# plc_esp32_programmer.net
KiCad netlist of a schematic drawn in EAGLE
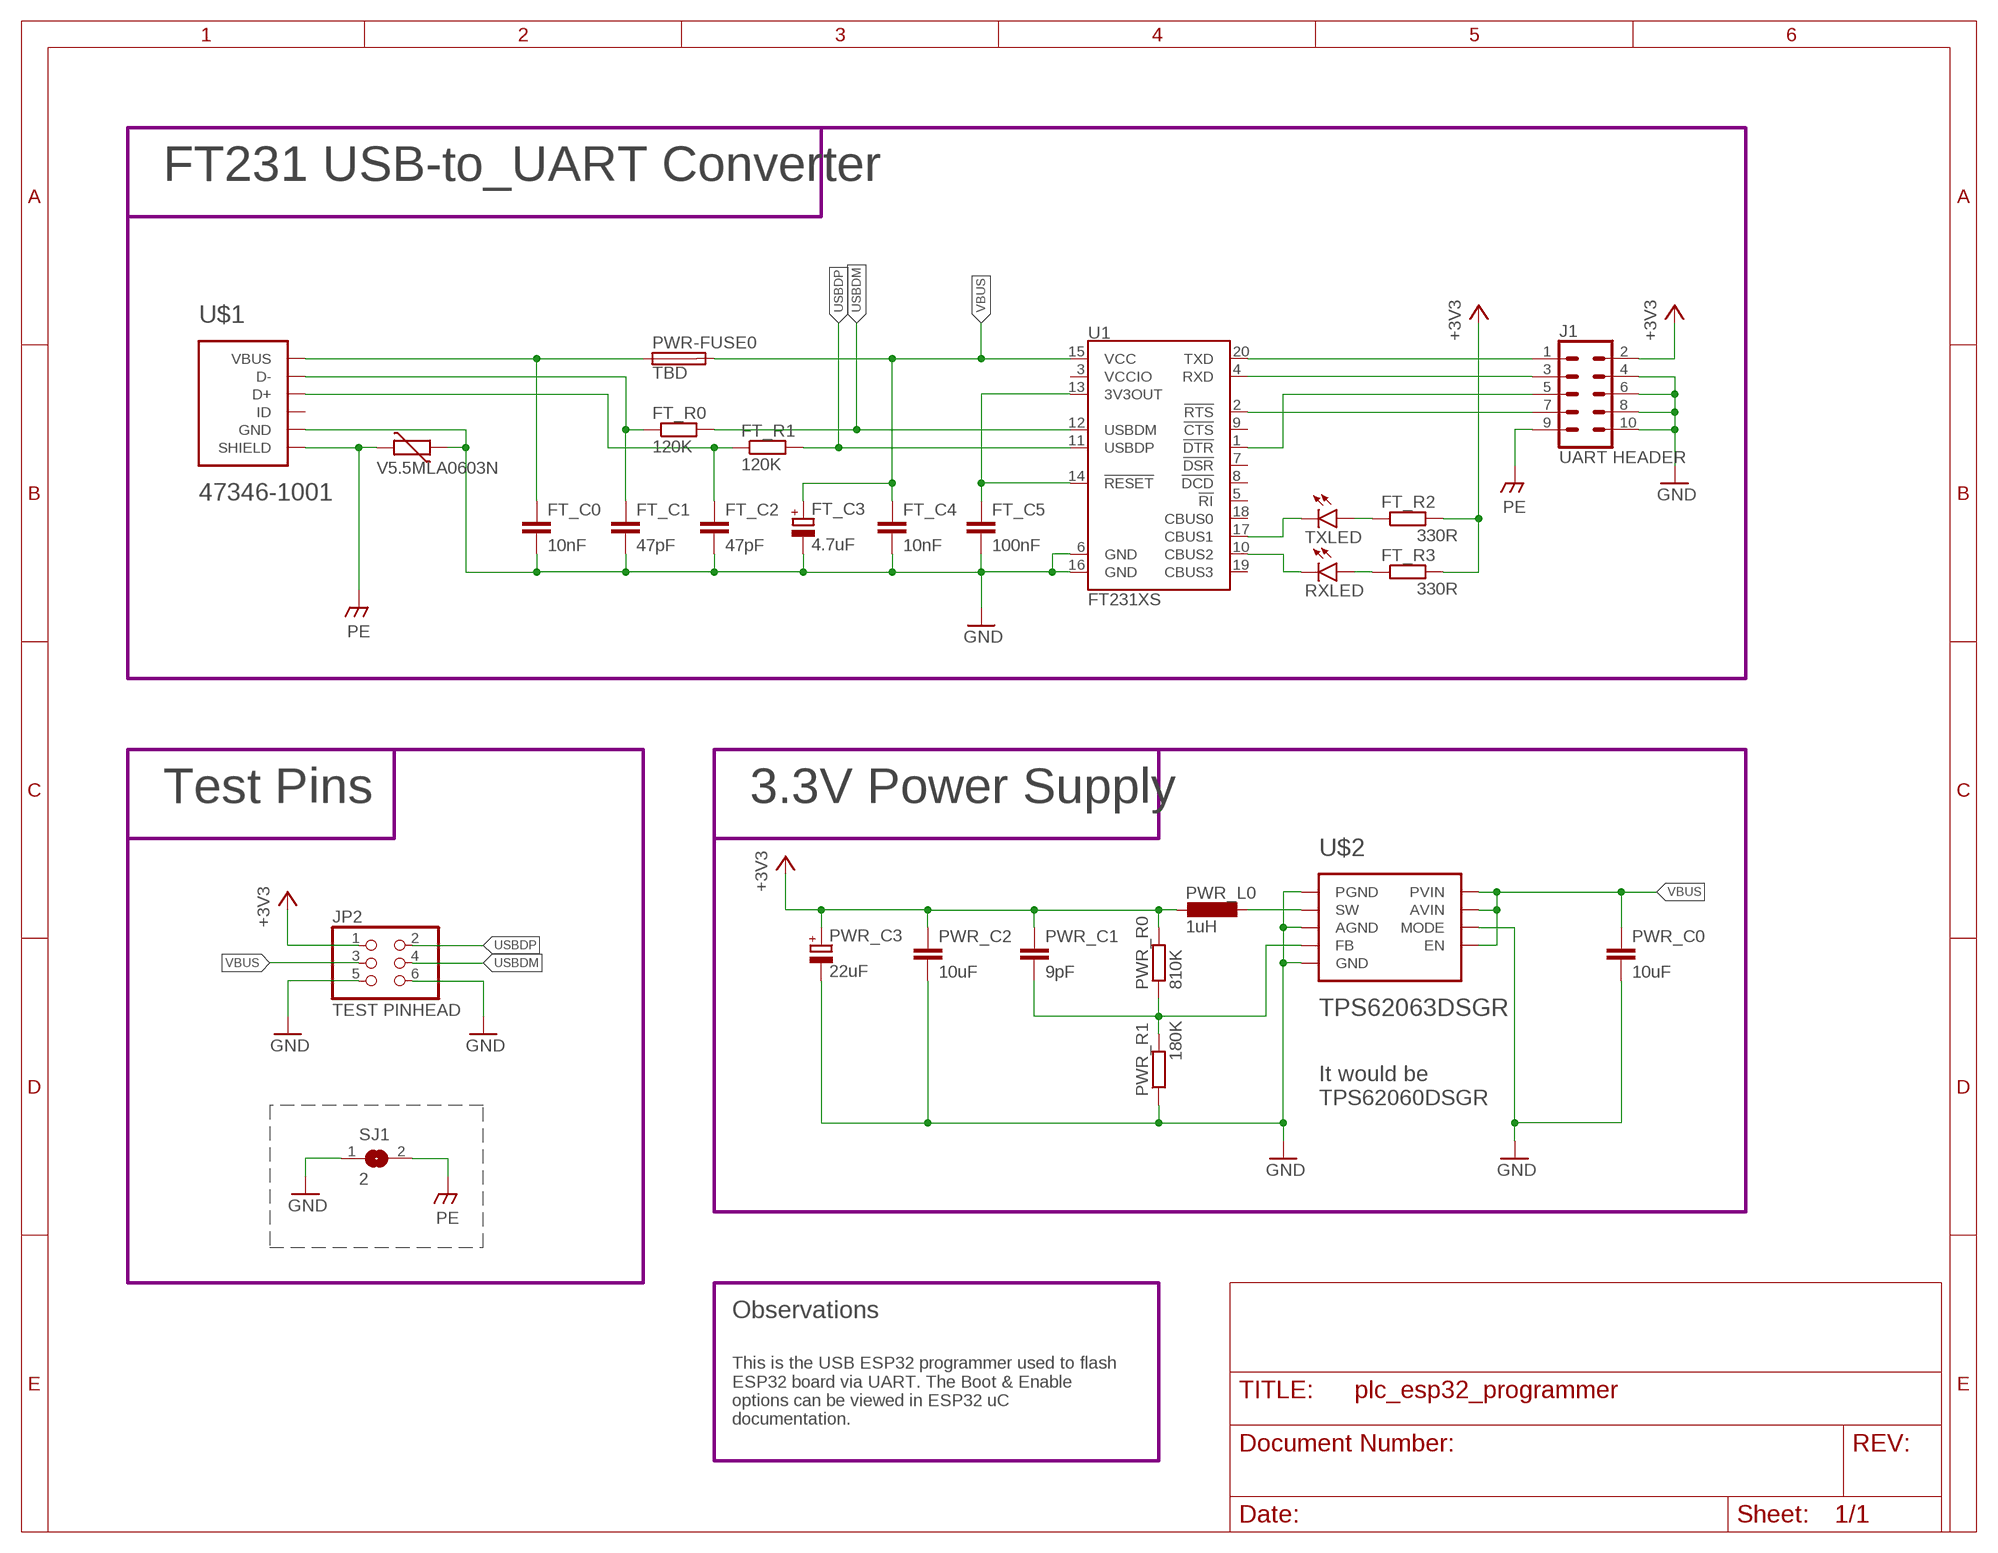
[diagram p0: schematic, sheet 1]

(export (version "E")
  (design (tool "Eeschema 10.0.6"))
  (components
    (comp (ref "FT_C0")
      (value "10nF")
      (footprint "eagle-import:C0402")
      (libsource (lib "eagle-import") (part "C-EUC0402"))
    )
    (comp (ref "FT_C1")
      (value "47pF")
      (footprint "eagle-import:C0402")
      (libsource (lib "eagle-import") (part "C-EUC0402"))
    )
    (comp (ref "FT_C2")
      (value "47pF")
      (footprint "eagle-import:C0402")
      (libsource (lib "eagle-import") (part "C-EUC0402"))
    )
    (comp (ref "FT_C3")
      (value "4.7uF")
      (footprint "eagle-import:SMC_B")
      (libsource (lib "eagle-import") (part "CPOL-EUSMCB"))
    )
    (comp (ref "FT_C4")
      (value "10nF")
      (footprint "eagle-import:C0402")
      (libsource (lib "eagle-import") (part "C-EUC0402"))
    )
    (comp (ref "FT_C5")
      (value "100nF")
      (footprint "eagle-import:C0402")
      (libsource (lib "eagle-import") (part "C-EUC0402"))
    )
    (comp (ref "FT_R0")
      (value "120K")
      (footprint "eagle-import:R0402")
      (libsource (lib "eagle-import") (part "R-EU_R0402"))
    )
    (comp (ref "FT_R1")
      (value "120K")
      (footprint "eagle-import:R0402")
      (libsource (lib "eagle-import") (part "R-EU_R0402"))
    )
    (comp (ref "FT_R2")
      (value "330R")
      (footprint "eagle-import:R0402")
      (libsource (lib "eagle-import") (part "R-EU_R0402"))
    )
    (comp (ref "FT_R3")
      (value "330R")
      (footprint "eagle-import:R0402")
      (libsource (lib "eagle-import") (part "R-EU_R0402"))
    )
    (comp (ref "J1")
      (value "UART HEADER")
      (footprint "eagle-import:2X5-SHROUDED_SMD")
      (libsource (lib "eagle-import") (part "CONN_05X2SHD_SMD"))
    )
    (comp (ref "JP2")
      (value "TEST PINHEAD")
      (footprint "eagle-import:2X03")
      (libsource (lib "eagle-import") (part "PINHD-2X3"))
    )
    (comp (ref "MCU_VAR1")
      (value "V5.5MLA0603N")
      (footprint "eagle-import:CT_CN0603")
      (libsource (lib "eagle-import") (part "VARISTORCN0603"))
    )
    (comp (ref "PWR-FUSE0")
      (value "TBD")
      (footprint "eagle-import:MF-SMDF050")
      (libsource (lib "eagle-import") (part "MF-SMDF050"))
    )
    (comp (ref "PWR_C0")
      (value "10uF")
      (footprint "eagle-import:C0603")
      (libsource (lib "eagle-import") (part "C-EUC0603"))
    )
    (comp (ref "PWR_C1")
      (value "9pF")
      (footprint "eagle-import:C0402")
      (libsource (lib "eagle-import") (part "C-EUC0402"))
    )
    (comp (ref "PWR_C2")
      (value "10uF")
      (footprint "eagle-import:C0603")
      (libsource (lib "eagle-import") (part "C-EUC0603"))
    )
    (comp (ref "PWR_C3")
      (value "22uF")
      (footprint "eagle-import:SMC_B")
      (libsource (lib "eagle-import") (part "CPOL-EUSMCB"))
    )
    (comp (ref "PWR_L0")
      (value "1uH")
      (footprint "eagle-import:L1210")
      (libsource (lib "eagle-import") (part "L-EUL1210"))
    )
    (comp (ref "PWR_R0")
      (value "810K")
      (footprint "eagle-import:R0402")
      (libsource (lib "eagle-import") (part "R-EU_R0402"))
    )
    (comp (ref "PWR_R1")
      (value "180K")
      (footprint "eagle-import:R0402")
      (libsource (lib "eagle-import") (part "R-EU_R0402"))
    )
    (comp (ref "RXLED")
      (value "LG_T679-E1F1-1")
      (footprint "eagle-import:PLCC2")
      (libsource (lib "eagle-import") (part "_T679-?-1E1F1LG"))
    )
    (comp (ref "SJ1") (value "2") (footprint "eagle-import:SJ") (libsource (lib "eagle-import") (part "SJ")))
    (comp (ref "TXLED")
      (value "LG_T679-E1F1-1")
      (footprint "eagle-import:PLCC2")
      (libsource (lib "eagle-import") (part "_T679-?-1E1F1LG"))
    )
    (comp (ref "U$1")
      (value "47346-1001")
      (footprint "eagle-import:47346-1001")
      (libsource (lib "eagle-import") (part "47346-1001"))
    )
    (comp (ref "U$2")
      (value "TPS62063DSGR")
      (footprint "eagle-import:WSON-8")
      (libsource (lib "eagle-import") (part "TPS62063DSGR"))
    )
    (comp (ref "U1")
      (value "FT231XS")
      (footprint "eagle-import:SSOP20_L")
      (libsource (lib "eagle-import") (part "FT231XS"))
    )
  )
  (nets
    (net (code "1") (name "+3V3") (class "Default")
      (node (ref "FT_R2") (pin "2") (pinfunction "2_2") (pintype "passive"))
      (node (ref "FT_R3") (pin "2") (pinfunction "2_2") (pintype "passive"))
      (node (ref "J1") (pin "2") (pinfunction "2_2") (pintype "passive"))
      (node (ref "JP2") (pin "1") (pinfunction "1_1") (pintype "passive"))
      (node (ref "PWR_C1") (pin "1") (pinfunction "1_1") (pintype "passive"))
      (node (ref "PWR_C2") (pin "1") (pinfunction "1_1") (pintype "passive"))
      (node (ref "PWR_C3") (pin "+") (pinfunction "+_+") (pintype "passive"))
      (node (ref "PWR_L0") (pin "2") (pinfunction "2_2") (pintype "passive"))
      (node (ref "PWR_R0") (pin "2") (pinfunction "2_2") (pintype "passive"))
    )
    (net (code "2") (name "GND") (class "Default")
      (node (ref "FT_C0") (pin "2") (pinfunction "2_2") (pintype "passive"))
      (node (ref "FT_C1") (pin "2") (pinfunction "2_2") (pintype "passive"))
      (node (ref "FT_C2") (pin "2") (pinfunction "2_2") (pintype "passive"))
      (node (ref "FT_C3") (pin "-") (pinfunction "-_-") (pintype "passive"))
      (node (ref "FT_C4") (pin "2") (pinfunction "2_2") (pintype "passive"))
      (node (ref "FT_C5") (pin "2") (pinfunction "2_2") (pintype "passive"))
      (node (ref "J1") (pin "10") (pinfunction "10_10") (pintype "passive"))
      (node (ref "J1") (pin "4") (pinfunction "4_4") (pintype "passive"))
      (node (ref "J1") (pin "6") (pinfunction "6_6") (pintype "passive"))
      (node (ref "J1") (pin "8") (pinfunction "8_8") (pintype "passive"))
      (node (ref "JP2") (pin "5") (pinfunction "5_5") (pintype "passive"))
      (node (ref "JP2") (pin "6") (pinfunction "6_6") (pintype "passive"))
      (node (ref "MCU_VAR1") (pin "1") (pinfunction "1_1") (pintype "passive"))
      (node (ref "PWR_C0") (pin "2") (pinfunction "2_2") (pintype "passive"))
      (node (ref "PWR_C2") (pin "2") (pinfunction "2_2") (pintype "passive"))
      (node (ref "PWR_C3") (pin "-") (pinfunction "-_-") (pintype "passive"))
      (node (ref "PWR_R1") (pin "1") (pinfunction "1_1") (pintype "passive"))
      (node (ref "SJ1") (pin "1") (pinfunction "1_1") (pintype "passive"))
      (node (ref "U$1") (pin "5") (pinfunction "GND_5") (pintype "bidirectional"))
      (node (ref "U$2") (pin "1") (pinfunction "PGND_1") (pintype "bidirectional"))
      (node (ref "U$2") (pin "10") (pinfunction "GND_10") (pintype "bidirectional"))
      (node (ref "U$2") (pin "11") (pinfunction "GND_11") (pintype "bidirectional"))
      (node (ref "U$2") (pin "3") (pinfunction "AGND_3") (pintype "bidirectional"))
      (node (ref "U$2") (pin "6") (pinfunction "MODE_6") (pintype "bidirectional"))
      (node (ref "U$2") (pin "9") (pinfunction "GND_9") (pintype "bidirectional"))
      (node (ref "U1") (pin "16") (pinfunction "GND_16") (pintype "bidirectional"))
      (node (ref "U1") (pin "6") (pinfunction "GND_6") (pintype "bidirectional"))
    )
    (net (code "3") (name "Net-(FT_R2-Pad1)") (class "Default")
      (node (ref "FT_R2") (pin "1") (pinfunction "1_1") (pintype "passive"))
      (node (ref "TXLED") (pin "A") (pinfunction "A_A") (pintype "passive"))
    )
    (net (code "4") (name "Net-(FT_R3-Pad1)") (class "Default")
      (node (ref "FT_R3") (pin "1") (pinfunction "1_1") (pintype "passive"))
      (node (ref "RXLED") (pin "A") (pinfunction "A_A") (pintype "passive"))
    )
    (net (code "5") (name "Net-(U$1-D+)") (class "Default")
      (node (ref "FT_C2") (pin "1") (pinfunction "1_1") (pintype "passive"))
      (node (ref "FT_R1") (pin "1") (pinfunction "1_1") (pintype "passive"))
      (node (ref "U$1") (pin "3") (pinfunction "D+_3") (pintype "bidirectional"))
    )
    (net (code "6") (name "Net-(U$1-D-)") (class "Default")
      (node (ref "FT_C1") (pin "1") (pinfunction "1_1") (pintype "passive"))
      (node (ref "FT_R0") (pin "1") (pinfunction "1_1") (pintype "passive"))
      (node (ref "U$1") (pin "2") (pinfunction "D-_2") (pintype "bidirectional"))
    )
    (net (code "7") (name "Net-(U$1-VBUS)") (class "Default")
      (node (ref "FT_C0") (pin "1") (pinfunction "1_1") (pintype "passive"))
      (node (ref "PWR-FUSE0") (pin "1") (pinfunction "1_1") (pintype "passive"))
      (node (ref "U$1") (pin "1") (pinfunction "VBUS_1") (pintype "bidirectional"))
    )
    (net (code "8") (name "Net-(U$2-FB)") (class "Default")
      (node (ref "PWR_C1") (pin "2") (pinfunction "2_2") (pintype "passive"))
      (node (ref "PWR_R0") (pin "1") (pinfunction "1_1") (pintype "passive"))
      (node (ref "PWR_R1") (pin "2") (pinfunction "2_2") (pintype "passive"))
      (node (ref "U$2") (pin "4") (pinfunction "FB_4") (pintype "bidirectional"))
    )
    (net (code "9") (name "Net-(U$2-SW)") (class "Default")
      (node (ref "PWR_L0") (pin "1") (pinfunction "1_1") (pintype "passive"))
      (node (ref "U$2") (pin "2") (pinfunction "SW_2") (pintype "bidirectional"))
    )
    (net (code "10") (name "Net-(U1-3V3OUT)") (class "Default")
      (node (ref "FT_C5") (pin "1") (pinfunction "1_1") (pintype "passive"))
      (node (ref "U1") (pin "13") (pinfunction "3V3OUT_13") (pintype "bidirectional"))
      (node (ref "U1") (pin "14") (pinfunction "~{RESET}_14") (pintype "bidirectional"))
    )
    (net (code "11") (name "Net-(U1-CBUS1)") (class "Default")
      (node (ref "TXLED") (pin "C") (pinfunction "C_C") (pintype "passive"))
      (node (ref "U1") (pin "17") (pinfunction "CBUS1_17") (pintype "bidirectional"))
    )
    (net (code "12") (name "Net-(U1-CBUS2)") (class "Default")
      (node (ref "RXLED") (pin "C") (pinfunction "C_C") (pintype "passive"))
      (node (ref "U1") (pin "10") (pinfunction "CBUS2_10") (pintype "bidirectional"))
    )
    (net (code "13") (name "Net-(U1-RXD)") (class "Default")
      (node (ref "J1") (pin "3") (pinfunction "3_3") (pintype "passive"))
      (node (ref "U1") (pin "4") (pinfunction "RXD_4") (pintype "bidirectional"))
    )
    (net (code "14") (name "Net-(U1-TXD)") (class "Default")
      (node (ref "J1") (pin "1") (pinfunction "1_1") (pintype "passive"))
      (node (ref "U1") (pin "20") (pinfunction "TXD_20") (pintype "bidirectional"))
    )
    (net (code "15") (name "Net-(U1-~{DTR})") (class "Default")
      (node (ref "J1") (pin "5") (pinfunction "5_5") (pintype "passive"))
      (node (ref "U1") (pin "1") (pinfunction "~{DTR}_1") (pintype "bidirectional"))
    )
    (net (code "16") (name "Net-(U1-~{RTS})") (class "Default")
      (node (ref "J1") (pin "7") (pinfunction "7_7") (pintype "passive"))
      (node (ref "U1") (pin "2") (pinfunction "~{RTS}_2") (pintype "bidirectional"))
    )
    (net (code "17") (name "PE") (class "Default")
      (node (ref "J1") (pin "9") (pinfunction "9_9") (pintype "passive"))
      (node (ref "MCU_VAR1") (pin "2") (pinfunction "2_2") (pintype "passive"))
      (node (ref "SJ1") (pin "2") (pinfunction "2_2") (pintype "passive"))
      (node (ref "U$1") (pin "10") (pinfunction "SHIELD_10") (pintype "bidirectional"))
      (node (ref "U$1") (pin "11") (pinfunction "SHIELD_11") (pintype "bidirectional"))
      (node (ref "U$1") (pin "6") (pinfunction "SHIELD_6") (pintype "bidirectional"))
      (node (ref "U$1") (pin "7") (pinfunction "SHIELD_7") (pintype "bidirectional"))
      (node (ref "U$1") (pin "8") (pinfunction "SHIELD_8") (pintype "bidirectional"))
      (node (ref "U$1") (pin "9") (pinfunction "SHIELD_9") (pintype "bidirectional"))
    )
    (net (code "18") (name "USBDM") (class "Default")
      (node (ref "FT_R0") (pin "2") (pinfunction "2_2") (pintype "passive"))
      (node (ref "JP2") (pin "4") (pinfunction "4_4") (pintype "passive"))
      (node (ref "U1") (pin "12") (pinfunction "USBDM_12") (pintype "bidirectional"))
    )
    (net (code "19") (name "USBDP") (class "Default")
      (node (ref "FT_R1") (pin "2") (pinfunction "2_2") (pintype "passive"))
      (node (ref "JP2") (pin "2") (pinfunction "2_2") (pintype "passive"))
      (node (ref "U1") (pin "11") (pinfunction "USBDP_11") (pintype "bidirectional"))
    )
    (net (code "20") (name "VBUS") (class "Default")
      (node (ref "FT_C3") (pin "+") (pinfunction "+_+") (pintype "passive"))
      (node (ref "FT_C4") (pin "1") (pinfunction "1_1") (pintype "passive"))
      (node (ref "JP2") (pin "3") (pinfunction "3_3") (pintype "passive"))
      (node (ref "PWR-FUSE0") (pin "2") (pinfunction "2_2") (pintype "passive"))
      (node (ref "PWR_C0") (pin "1") (pinfunction "1_1") (pintype "passive"))
      (node (ref "U$2") (pin "5") (pinfunction "EN_5") (pintype "bidirectional"))
      (node (ref "U$2") (pin "7") (pinfunction "AVIN_7") (pintype "bidirectional"))
      (node (ref "U$2") (pin "8") (pinfunction "PVIN_8") (pintype "bidirectional"))
      (node (ref "U1") (pin "15") (pinfunction "VCC_15") (pintype "bidirectional"))
    )
    (net (code "21") (name "unconnected-(U$1-ID-Pad4)") (class "Default")
      (node (ref "U$1") (pin "4") (pinfunction "ID_4") (pintype "bidirectional"))
    )
    (net (code "22") (name "unconnected-(U1-CBUS0-Pad18)") (class "Default")
      (node (ref "U1") (pin "18") (pinfunction "CBUS0_18") (pintype "bidirectional"))
    )
    (net (code "23") (name "unconnected-(U1-CBUS3-Pad19)") (class "Default")
      (node (ref "U1") (pin "19") (pinfunction "CBUS3_19") (pintype "bidirectional"))
    )
    (net (code "24") (name "unconnected-(U1-VCCIO-Pad3)") (class "Default")
      (node (ref "U1") (pin "3") (pinfunction "VCCIO_3") (pintype "bidirectional"))
    )
    (net (code "25") (name "unconnected-(U1-~{CTS}-Pad9)") (class "Default")
      (node (ref "U1") (pin "9") (pinfunction "~{CTS}_9") (pintype "bidirectional"))
    )
    (net (code "26") (name "unconnected-(U1-~{DCD}-Pad8)") (class "Default")
      (node (ref "U1") (pin "8") (pinfunction "~{DCD}_8") (pintype "bidirectional"))
    )
    (net (code "27") (name "unconnected-(U1-~{DSR}-Pad7)") (class "Default")
      (node (ref "U1") (pin "7") (pinfunction "~{DSR}_7") (pintype "bidirectional"))
    )
    (net (code "28") (name "unconnected-(U1-~{RI}-Pad5)") (class "Default")
      (node (ref "U1") (pin "5") (pinfunction "~{RI}_5") (pintype "bidirectional"))
    )
  )
)
